# chipchestra-v05-joystick.net
KiCad netlist of a schematic drawn in EAGLE
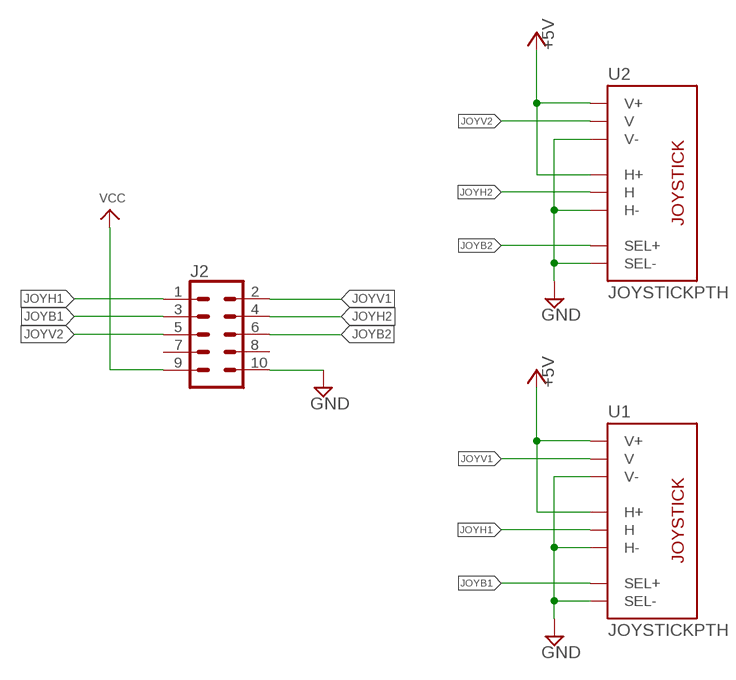
[diagram p0: schematic, sheet 1]

(export (version "E")
  (design (tool "Eeschema 10.0.6"))
  (components
    (comp (ref "J2")
      (value "CONN_05X2SHD_LOCK")
      (footprint "eagle-import:2X5-SHROUDED_LOCK")
      (libsource (lib "eagle-import") (part "CONN_05X2SHD_LOCK"))
    )
    (comp (ref "U1")
      (value "JOYSTICKPTH")
      (footprint "eagle-import:JOYSTICK")
      (libsource (lib "eagle-import") (part "JOYSTICKPTH"))
    )
    (comp (ref "U2")
      (value "JOYSTICKPTH")
      (footprint "eagle-import:JOYSTICK")
      (libsource (lib "eagle-import") (part "JOYSTICKPTH"))
    )
  )
  (nets
    (net (code "1") (name "+5V") (class "Default")
      (node (ref "U1") (pin "H1") (pinfunction "H+_H1") (pintype "bidirectional"))
      (node (ref "U1") (pin "V1") (pinfunction "V+_V1") (pintype "bidirectional"))
      (node (ref "U2") (pin "H1") (pinfunction "H+_H1") (pintype "bidirectional"))
      (node (ref "U2") (pin "V1") (pinfunction "V+_V1") (pintype "bidirectional"))
    )
    (net (code "2") (name "GND") (class "Default")
      (node (ref "J2") (pin "10") (pinfunction "10_10") (pintype "passive"))
      (node (ref "U1") (pin "B2A") (pinfunction "SEL-_B2A") (pintype "bidirectional"))
      (node (ref "U1") (pin "H3") (pinfunction "H-_H3") (pintype "bidirectional"))
      (node (ref "U1") (pin "V3") (pinfunction "V-_V3") (pintype "bidirectional"))
      (node (ref "U2") (pin "B2A") (pinfunction "SEL-_B2A") (pintype "bidirectional"))
      (node (ref "U2") (pin "H3") (pinfunction "H-_H3") (pintype "bidirectional"))
      (node (ref "U2") (pin "V3") (pinfunction "V-_V3") (pintype "bidirectional"))
    )
    (net (code "3") (name "JOYB1") (class "Default")
      (node (ref "J2") (pin "3") (pinfunction "3_3") (pintype "passive"))
      (node (ref "U1") (pin "B1A") (pinfunction "SEL+_B1A") (pintype "bidirectional"))
    )
    (net (code "4") (name "JOYB2") (class "Default")
      (node (ref "J2") (pin "6") (pinfunction "6_6") (pintype "passive"))
      (node (ref "U2") (pin "B1A") (pinfunction "SEL+_B1A") (pintype "bidirectional"))
    )
    (net (code "5") (name "JOYH1") (class "Default")
      (node (ref "J2") (pin "1") (pinfunction "1_1") (pintype "passive"))
      (node (ref "U1") (pin "H2") (pinfunction "H_H2") (pintype "bidirectional"))
    )
    (net (code "6") (name "JOYH2") (class "Default")
      (node (ref "J2") (pin "4") (pinfunction "4_4") (pintype "passive"))
      (node (ref "U2") (pin "H2") (pinfunction "H_H2") (pintype "bidirectional"))
    )
    (net (code "7") (name "JOYV1") (class "Default")
      (node (ref "J2") (pin "2") (pinfunction "2_2") (pintype "passive"))
      (node (ref "U1") (pin "V2") (pinfunction "V_V2") (pintype "bidirectional"))
    )
    (net (code "8") (name "JOYV2") (class "Default")
      (node (ref "J2") (pin "5") (pinfunction "5_5") (pintype "passive"))
      (node (ref "U2") (pin "V2") (pinfunction "V_V2") (pintype "bidirectional"))
    )
    (net (code "9") (name "VCC") (class "Default")
      (node (ref "J2") (pin "9") (pinfunction "9_9") (pintype "passive"))
    )
    (net (code "10") (name "unconnected-(J2-Pad7)") (class "Default")
      (node (ref "J2") (pin "7") (pinfunction "7_7") (pintype "passive"))
    )
    (net (code "11") (name "unconnected-(J2-Pad8)") (class "Default")
      (node (ref "J2") (pin "8") (pinfunction "8_8") (pintype "passive"))
    )
  )
)
